# Zero-Cross_Detection.net
KiCad netlist of a schematic drawn in Altium Designer
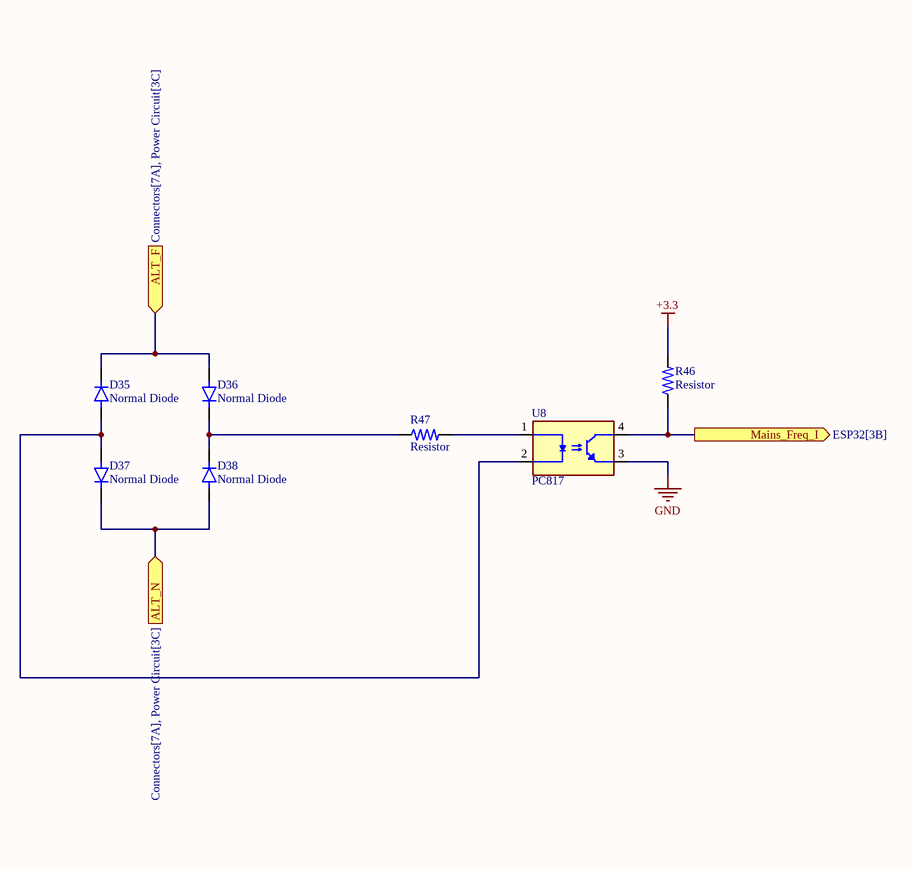
[diagram p0: Zero-Cross_Detection.SchDoc]

(export (version "E")
  (design (tool "Eeschema 10.0.6"))
  (components
    (comp (ref "D35")
      (value "Normal Diode")
      (footprint "Common Trhough Hole")
      (fields (field (name "MF") "NTE Electronics, Inc.") (field (name "MP") "1N4007"))
      (libsource (lib "Diodes Through Hole") (part "Normal Diode"))
    )
    (comp (ref "D36")
      (value "Normal Diode")
      (footprint "Common Trhough Hole")
      (fields (field (name "MF") "NTE Electronics, Inc.") (field (name "MP") "1N4007"))
      (libsource (lib "Diodes Through Hole") (part "Normal Diode"))
    )
    (comp (ref "D37")
      (value "Normal Diode")
      (footprint "Common Trhough Hole")
      (fields (field (name "MF") "NTE Electronics, Inc.") (field (name "MP") "1N4007"))
      (libsource (lib "Diodes Through Hole") (part "Normal Diode"))
    )
    (comp (ref "D38")
      (value "Normal Diode")
      (footprint "Common Trhough Hole")
      (fields (field (name "MF") "NTE Electronics, Inc.") (field (name "MP") "1N4007"))
      (libsource (lib "Diodes Through Hole") (part "Normal Diode"))
    )
    (comp (ref "R46")
      (value "Resistor")
      (footprint "Resistor_Through Hole")
      (fields
        (field (name "MP") "2-2176053-0")
        (field (name "TOLERANCE") "1%")
        (field (name "MF") "TE Connectivity")
      )
      (libsource (lib "Resistors Through Hole") (part "Resistor"))
    )
    (comp (ref "R47")
      (value "Resistor")
      (footprint "Resistor_Through Hole")
      (fields
        (field (name "MP") "2-2176053-0")
        (field (name "TOLERANCE") "1%")
        (field (name "MF") "TE Connectivity")
      )
      (libsource (lib "Resistors Through Hole") (part "Resistor"))
    )
    (comp (ref "U8")
      (value "PC817")
      (footprint "PC817")
      (description "Optoisolator Transistor Output - 1 Channel 4-DIP")
      (fields (field (name "MP") "PC817X3NSZ1B") (field (name "MF") "Sharp Microelectronics"))
      (libsource (lib "Optocoupler Through Hole") (part "PC817"))
    )
  )
  (nets
    (net (code "1") (name "+3.3") (class "Default")
      (node (ref "R46") (pin "2") (pinfunction "2_2") (pintype "passive"))
    )
    (net (code "2") (name "/ALT_F") (class "Default")
      (node (ref "D35") (pin "1") (pinfunction "K_1") (pintype "passive"))
      (node (ref "D36") (pin "2") (pinfunction "A_2") (pintype "passive"))
    )
    (net (code "3") (name "/ALT_N") (class "Default")
      (node (ref "D37") (pin "1") (pinfunction "K_1") (pintype "passive"))
      (node (ref "D38") (pin "2") (pinfunction "A_2") (pintype "passive"))
    )
    (net (code "4") (name "/Mains_Freq_I") (class "Default")
      (node (ref "R46") (pin "1") (pinfunction "1_1") (pintype "passive"))
      (node (ref "U8") (pin "4") (pinfunction "COLLECTOR_4") (pintype "passive"))
    )
    (net (code "5") (name "GND") (class "Default")
      (node (ref "U8") (pin "3") (pinfunction "EMITTER_3") (pintype "passive"))
    )
    (net (code "6") (name "Net-(D35-A)") (class "Default")
      (node (ref "D35") (pin "2") (pinfunction "A_2") (pintype "passive"))
      (node (ref "D37") (pin "2") (pinfunction "A_2") (pintype "passive"))
      (node (ref "U8") (pin "2") (pinfunction "CATHODE_2") (pintype "passive"))
    )
    (net (code "7") (name "Net-(D36-K)") (class "Default")
      (node (ref "D36") (pin "1") (pinfunction "K_1") (pintype "passive"))
      (node (ref "D38") (pin "1") (pinfunction "K_1") (pintype "passive"))
      (node (ref "R47") (pin "1") (pinfunction "1_1") (pintype "passive"))
    )
    (net (code "8") (name "Net-(U8-ANODE)") (class "Default")
      (node (ref "R47") (pin "2") (pinfunction "2_2") (pintype "passive"))
      (node (ref "U8") (pin "1") (pinfunction "ANODE_1") (pintype "passive"))
    )
  )
)
